# bubble_size_sensor.net
KiCad netlist of a schematic drawn in EAGLE
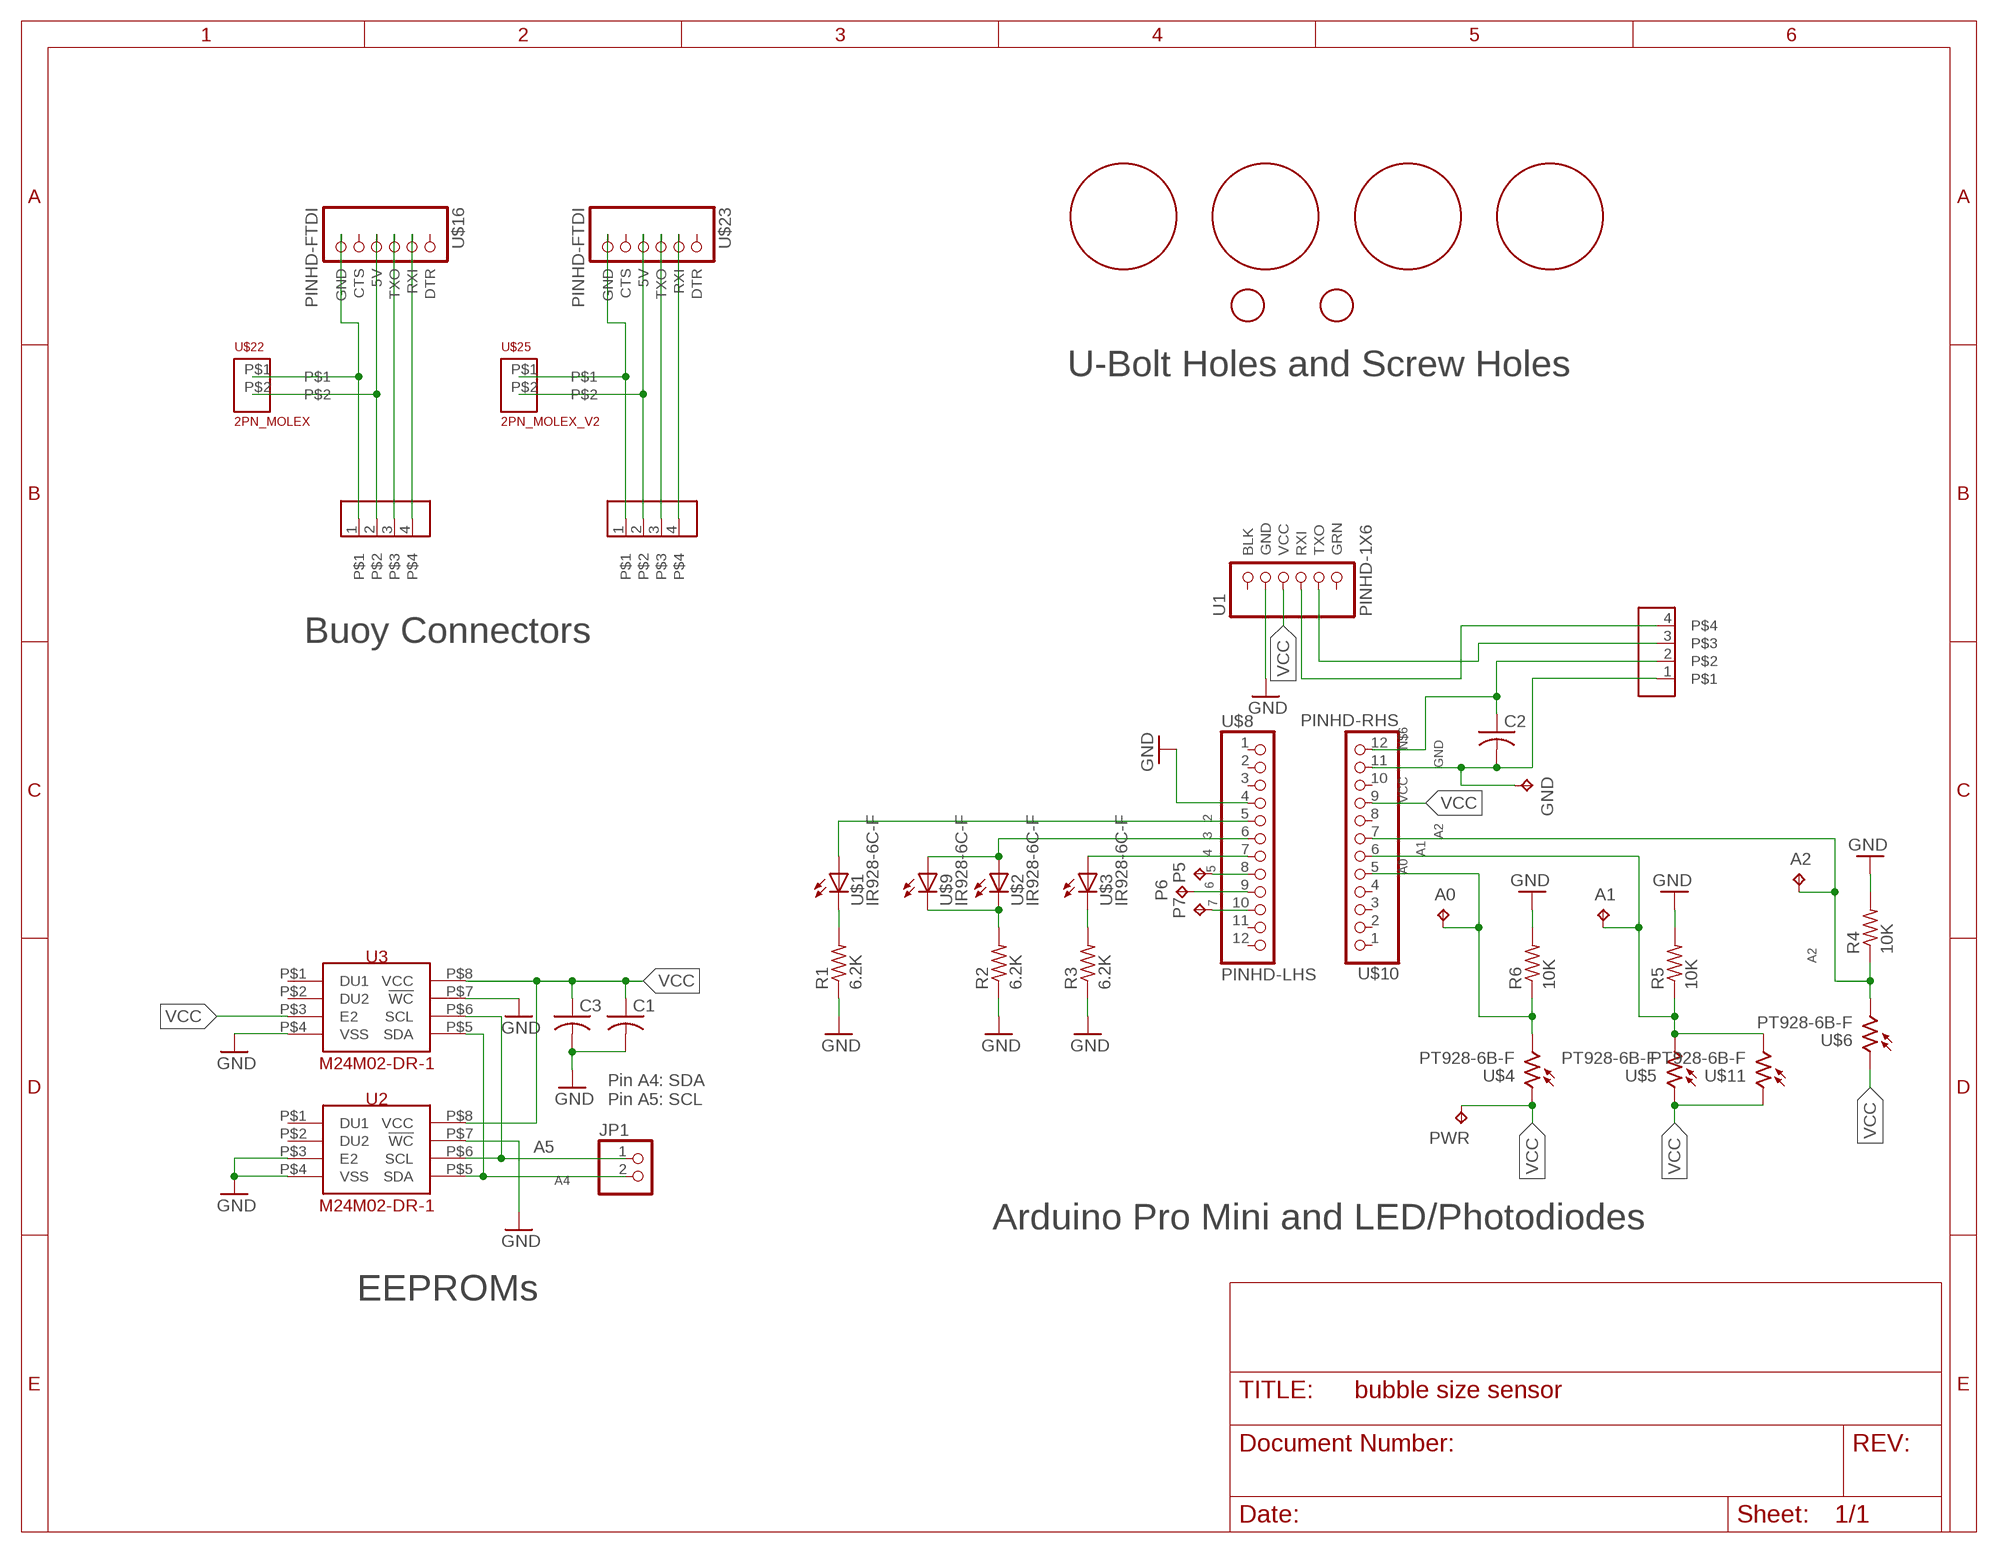
[diagram p0: schematic, sheet 1]

(export (version "E")
  (design (tool "Eeschema 10.0.6"))
  (components
    (comp (ref "A0")
      (value "TPPAD1-13")
      (footprint "eagle-import:P1-13")
      (libsource (lib "eagle-import") (part "TPPAD1-13"))
    )
    (comp (ref "A1")
      (value "TPPAD1-13")
      (footprint "eagle-import:P1-13")
      (libsource (lib "eagle-import") (part "TPPAD1-13"))
    )
    (comp (ref "A2")
      (value "TPPAD1-13")
      (footprint "eagle-import:P1-13")
      (libsource (lib "eagle-import") (part "TPPAD1-13"))
    )
    (comp (ref "C1")
      (value "C-USC0603")
      (footprint "eagle-import:C0603")
      (libsource (lib "eagle-import") (part "C-USC0603"))
    )
    (comp (ref "C2")
      (value "C-USC1210")
      (footprint "eagle-import:C1210")
      (libsource (lib "eagle-import") (part "C-USC1210"))
    )
    (comp (ref "C3")
      (value "C-USC0603")
      (footprint "eagle-import:C0603")
      (libsource (lib "eagle-import") (part "C-USC0603"))
    )
    (comp (ref "GND")
      (value "TPPAD1-13")
      (footprint "eagle-import:P1-13")
      (libsource (lib "eagle-import") (part "TPPAD1-13"))
    )
    (comp (ref "H$13")
      (value "M2_SCREW_HOLE")
      (footprint "eagle-import:M2_SCREW_HOLE")
      (libsource (lib "eagle-import") (part "M2_SCREW_HOLE"))
    )
    (comp (ref "H$15")
      (value "M2_SCREW_HOLE")
      (footprint "eagle-import:M2_SCREW_HOLE")
      (libsource (lib "eagle-import") (part "M2_SCREW_HOLE"))
    )
    (comp (ref "H$17")
      (value "UBOLT_HOLE")
      (footprint "eagle-import:UBOLT_HOLE")
      (libsource (lib "eagle-import") (part "UBOLT_HOLE"))
    )
    (comp (ref "H$18")
      (value "UBOLT_HOLE")
      (footprint "eagle-import:UBOLT_HOLE")
      (libsource (lib "eagle-import") (part "UBOLT_HOLE"))
    )
    (comp (ref "H$19")
      (value "UBOLT_HOLE")
      (footprint "eagle-import:UBOLT_HOLE")
      (libsource (lib "eagle-import") (part "UBOLT_HOLE"))
    )
    (comp (ref "H$20")
      (value "UBOLT_HOLE")
      (footprint "eagle-import:UBOLT_HOLE")
      (libsource (lib "eagle-import") (part "UBOLT_HOLE"))
    )
    (comp (ref "JP1")
      (value "PINHD-1X2")
      (footprint "eagle-import:1X02")
      (libsource (lib "eagle-import") (part "PINHD-1X2"))
    )
    (comp (ref "P5")
      (value "TPPAD1-13")
      (footprint "eagle-import:P1-13")
      (libsource (lib "eagle-import") (part "TPPAD1-13"))
    )
    (comp (ref "P6")
      (value "TPPAD1-13")
      (footprint "eagle-import:P1-13")
      (libsource (lib "eagle-import") (part "TPPAD1-13"))
    )
    (comp (ref "P7")
      (value "TPPAD1-13")
      (footprint "eagle-import:P1-13")
      (libsource (lib "eagle-import") (part "TPPAD1-13"))
    )
    (comp (ref "PWR")
      (value "TPPAD1-13")
      (footprint "eagle-import:P1-13")
      (libsource (lib "eagle-import") (part "TPPAD1-13"))
    )
    (comp (ref "R1")
      (value "6.2K")
      (footprint "eagle-import:R0603")
      (libsource (lib "eagle-import") (part "R-US_R0603"))
    )
    (comp (ref "R2")
      (value "6.2K")
      (footprint "eagle-import:R0603")
      (libsource (lib "eagle-import") (part "R-US_R0603"))
    )
    (comp (ref "R3")
      (value "6.2K")
      (footprint "eagle-import:R0603")
      (libsource (lib "eagle-import") (part "R-US_R0603"))
    )
    (comp (ref "R4")
      (value "10K")
      (footprint "eagle-import:R0603")
      (libsource (lib "eagle-import") (part "R-US_R0603"))
    )
    (comp (ref "R5")
      (value "10K")
      (footprint "eagle-import:R0603")
      (libsource (lib "eagle-import") (part "R-US_R0603"))
    )
    (comp (ref "R6")
      (value "10K")
      (footprint "eagle-import:R0603")
      (libsource (lib "eagle-import") (part "R-US_R0603"))
    )
    (comp (ref "U$1")
      (value "IR928-6C-F")
      (footprint "eagle-import:LED_LAYOUT")
      (libsource (lib "eagle-import") (part "IR928-6C-F"))
    )
    (comp (ref "U$2")
      (value "IR928-6C-F")
      (footprint "eagle-import:LED_LAYOUT")
      (libsource (lib "eagle-import") (part "IR928-6C-F"))
    )
    (comp (ref "U$3")
      (value "IR928-6C-F")
      (footprint "eagle-import:LED_LAYOUT")
      (libsource (lib "eagle-import") (part "IR928-6C-F"))
    )
    (comp (ref "U$4")
      (value "PT928-6B-F")
      (footprint "eagle-import:LED_LAYOUT")
      (libsource (lib "eagle-import") (part "PT928-6B-F"))
    )
    (comp (ref "U$5")
      (value "PT928-6B-F")
      (footprint "eagle-import:LED_LAYOUT")
      (libsource (lib "eagle-import") (part "PT928-6B-F"))
    )
    (comp (ref "U$6")
      (value "PT928-6B-F")
      (footprint "eagle-import:LED_LAYOUT")
      (libsource (lib "eagle-import") (part "PT928-6B-F"))
    )
    (comp (ref "U$8")
      (value "PINHD-LHS")
      (footprint "eagle-import:1X12")
      (libsource (lib "eagle-import") (part "PINHD-LHS"))
    )
    (comp (ref "U$9")
      (value "IR928-6C-F")
      (footprint "eagle-import:LED_LAYOUT")
      (libsource (lib "eagle-import") (part "IR928-6C-F"))
    )
    (comp (ref "U$10")
      (value "PINHD-RHS")
      (footprint "eagle-import:1X12")
      (libsource (lib "eagle-import") (part "PINHD-RHS"))
    )
    (comp (ref "U$11")
      (value "PT928-6B-F")
      (footprint "eagle-import:LED_LAYOUT")
      (libsource (lib "eagle-import") (part "PT928-6B-F"))
    )
    (comp (ref "U$14")
      (value "MICROFIT3.0_4POS_SMD")
      (footprint "eagle-import:MICRO_FIT3.0_4POS-SM")
      (libsource (lib "eagle-import") (part "MICROFIT3.0_4POS_SMD"))
    )
    (comp (ref "U$16")
      (value "PINHD-FTDI")
      (footprint "eagle-import:1X6")
      (libsource (lib "eagle-import") (part "PINHD-FTDI"))
    )
    (comp (ref "U$21")
      (value "MICROFIT3.0_4POS_SMD")
      (footprint "eagle-import:MICRO_FIT3.0_4POS-SM")
      (libsource (lib "eagle-import") (part "MICROFIT3.0_4POS_SMD"))
    )
    (comp (ref "U$22")
      (value "2PN_MOLEX")
      (footprint "eagle-import:2PN_MOLEX")
      (libsource (lib "eagle-import") (part "2PN_MOLEX"))
    )
    (comp (ref "U$23")
      (value "PINHD-FTDI")
      (footprint "eagle-import:1X6")
      (libsource (lib "eagle-import") (part "PINHD-FTDI"))
    )
    (comp (ref "U$24")
      (value "MICROFIT3.0_4POS_SMD")
      (footprint "eagle-import:MICRO_FIT3.0_4POS-SM")
      (libsource (lib "eagle-import") (part "MICROFIT3.0_4POS_SMD"))
    )
    (comp (ref "U$25")
      (value "2PN_MOLEX_V2")
      (footprint "eagle-import:2PN_MOLEX_V2")
      (libsource (lib "eagle-import") (part "2PN_MOLEX_V2"))
    )
    (comp (ref "U1")
      (value "PINHD-1X6")
      (footprint "eagle-import:1X6")
      (libsource (lib "eagle-import") (part "PINHD-1X6"))
    )
    (comp (ref "U2")
      (value "M24M02-DR-1")
      (footprint "eagle-import:SO8N")
      (fields
        (field (name "MANPARTNUMBER") "M24M02-DRMN6TP")
        (field (name "MANUFACTURER") "STMicroelectronics")
        (field (name "PARTNUMBER") "497-11600-1-ND")
      )
      (libsource (lib "eagle-import") (part "M24M02-DR-1"))
    )
    (comp (ref "U3")
      (value "M24M02-DR-1")
      (footprint "eagle-import:SO8N")
      (fields
        (field (name "MANPARTNUMBER") "M24M02-DRMN6TP")
        (field (name "MANUFACTURER") "STMicroelectronics")
        (field (name "PARTNUMBER") "497-11600-1-ND")
      )
      (libsource (lib "eagle-import") (part "M24M02-DR-1"))
    )
  )
  (nets
    (net (code "1") (name "/2") (class "Default")
      (node (ref "U$1") (pin "PWR") (pinfunction "PWR_PWR") (pintype "passive"))
      (node (ref "U$8") (pin "5") (pinfunction "2_5") (pintype "passive"))
    )
    (net (code "2") (name "/3") (class "Default")
      (node (ref "U$2") (pin "PWR") (pinfunction "PWR_PWR") (pintype "passive"))
      (node (ref "U$8") (pin "6") (pinfunction "3_6") (pintype "passive"))
      (node (ref "U$9") (pin "PWR") (pinfunction "PWR_PWR") (pintype "passive"))
    )
    (net (code "3") (name "/4") (class "Default")
      (node (ref "U$3") (pin "PWR") (pinfunction "PWR_PWR") (pintype "passive"))
      (node (ref "U$8") (pin "7") (pinfunction "4_7") (pintype "passive"))
    )
    (net (code "4") (name "/5") (class "Default")
      (node (ref "P5") (pin "TP") (pinfunction "TP_TP") (pintype "input"))
      (node (ref "U$8") (pin "8") (pinfunction "5_8") (pintype "passive"))
    )
    (net (code "5") (name "/6") (class "Default")
      (node (ref "P6") (pin "TP") (pinfunction "TP_TP") (pintype "input"))
      (node (ref "U$8") (pin "9") (pinfunction "6_9") (pintype "passive"))
    )
    (net (code "6") (name "/7") (class "Default")
      (node (ref "P7") (pin "TP") (pinfunction "TP_TP") (pintype "input"))
      (node (ref "U$8") (pin "10") (pinfunction "7_10") (pintype "passive"))
    )
    (net (code "7") (name "/A0") (class "Default")
      (node (ref "A0") (pin "TP") (pinfunction "TP_TP") (pintype "input"))
      (node (ref "R6") (pin "1") (pinfunction "1_1") (pintype "passive"))
      (node (ref "U$10") (pin "5") (pinfunction "A3_5") (pintype "passive"))
      (node (ref "U$4") (pin "RSTR") (pinfunction "RSTR_RSTR") (pintype "passive"))
    )
    (net (code "8") (name "/A1") (class "Default")
      (node (ref "A1") (pin "TP") (pinfunction "TP_TP") (pintype "input"))
      (node (ref "R5") (pin "1") (pinfunction "1_1") (pintype "passive"))
      (node (ref "U$10") (pin "6") (pinfunction "A2_6") (pintype "passive"))
      (node (ref "U$11") (pin "RSTR") (pinfunction "RSTR_RSTR") (pintype "passive"))
      (node (ref "U$5") (pin "RSTR") (pinfunction "RSTR_RSTR") (pintype "passive"))
    )
    (net (code "9") (name "/A2") (class "Default")
      (node (ref "A2") (pin "TP") (pinfunction "TP_TP") (pintype "input"))
      (node (ref "R4") (pin "1") (pinfunction "1_1") (pintype "passive"))
      (node (ref "U$10") (pin "7") (pinfunction "A1_7") (pintype "passive"))
      (node (ref "U$6") (pin "RSTR") (pinfunction "RSTR_RSTR") (pintype "passive"))
    )
    (net (code "10") (name "/A4") (class "Default")
      (node (ref "JP1") (pin "2") (pinfunction "2_2") (pintype "passive"))
      (node (ref "U2") (pin "P$5") (pinfunction "SDA_P$5") (pintype "bidirectional"))
      (node (ref "U3") (pin "P$5") (pinfunction "SDA_P$5") (pintype "bidirectional"))
    )
    (net (code "11") (name "/A5") (class "Default")
      (node (ref "JP1") (pin "1") (pinfunction "1_1") (pintype "passive"))
      (node (ref "U2") (pin "P$6") (pinfunction "SCL_P$6") (pintype "input"))
      (node (ref "U3") (pin "P$6") (pinfunction "SCL_P$6") (pintype "input"))
    )
    (net (code "12") (name "/N$6") (class "Default")
      (node (ref "C2") (pin "1") (pinfunction "1_1") (pintype "passive"))
      (node (ref "U$10") (pin "12") (pinfunction "10_12") (pintype "passive"))
      (node (ref "U$14") (pin "2") (pinfunction "P$2_2") (pintype "bidirectional"))
    )
    (net (code "13") (name "GND") (class "Default")
      (node (ref "C1") (pin "2") (pinfunction "2_2") (pintype "passive"))
      (node (ref "C2") (pin "2") (pinfunction "2_2") (pintype "passive"))
      (node (ref "C3") (pin "2") (pinfunction "2_2") (pintype "passive"))
      (node (ref "GND") (pin "TP") (pinfunction "TP_TP") (pintype "input"))
      (node (ref "R1") (pin "1") (pinfunction "1_1") (pintype "passive"))
      (node (ref "R2") (pin "1") (pinfunction "1_1") (pintype "passive"))
      (node (ref "R3") (pin "1") (pinfunction "1_1") (pintype "passive"))
      (node (ref "R4") (pin "2") (pinfunction "2_2") (pintype "passive"))
      (node (ref "R5") (pin "2") (pinfunction "2_2") (pintype "passive"))
      (node (ref "R6") (pin "2") (pinfunction "2_2") (pintype "passive"))
      (node (ref "U$10") (pin "11") (pinfunction "11_11") (pintype "passive"))
      (node (ref "U$14") (pin "1") (pinfunction "P$1_1") (pintype "bidirectional"))
      (node (ref "U$8") (pin "4") (pinfunction "GND_4") (pintype "passive"))
      (node (ref "U1") (pin "2") (pinfunction "GND_2") (pintype "bidirectional"))
      (node (ref "U2") (pin "P$3") (pinfunction "E2_P$3") (pintype "input"))
      (node (ref "U2") (pin "P$4") (pinfunction "VSS_P$4") (pintype "power_in"))
      (node (ref "U2") (pin "P$7") (pinfunction "~{WC}_P$7") (pintype "input"))
      (node (ref "U3") (pin "P$4") (pinfunction "VSS_P$4") (pintype "power_in"))
      (node (ref "U3") (pin "P$7") (pinfunction "~{WC}_P$7") (pintype "input"))
    )
    (net (code "14") (name "Net-(R1-Pad2)") (class "Default")
      (node (ref "R1") (pin "2") (pinfunction "2_2") (pintype "passive"))
      (node (ref "U$1") (pin "RSTR") (pinfunction "RSTR_RSTR") (pintype "passive"))
    )
    (net (code "15") (name "Net-(R2-Pad2)") (class "Default")
      (node (ref "R2") (pin "2") (pinfunction "2_2") (pintype "passive"))
      (node (ref "U$2") (pin "RSTR") (pinfunction "RSTR_RSTR") (pintype "passive"))
      (node (ref "U$9") (pin "RSTR") (pinfunction "RSTR_RSTR") (pintype "passive"))
    )
    (net (code "16") (name "Net-(R3-Pad2)") (class "Default")
      (node (ref "R3") (pin "2") (pinfunction "2_2") (pintype "passive"))
      (node (ref "U$3") (pin "RSTR") (pinfunction "RSTR_RSTR") (pintype "passive"))
    )
    (net (code "17") (name "Net-(U$14-P$3)") (class "Default")
      (node (ref "U$14") (pin "3") (pinfunction "P$3_3") (pintype "bidirectional"))
      (node (ref "U1") (pin "5") (pinfunction "TXO_5") (pintype "bidirectional"))
    )
    (net (code "18") (name "Net-(U$14-P$4)") (class "Default")
      (node (ref "U$14") (pin "4") (pinfunction "P$4_4") (pintype "bidirectional"))
      (node (ref "U1") (pin "4") (pinfunction "RXI_4") (pintype "bidirectional"))
    )
    (net (code "19") (name "Net-(U$16-5V)") (class "Default")
      (node (ref "U$16") (pin "4") (pinfunction "5V_4") (pintype "bidirectional"))
      (node (ref "U$21") (pin "2") (pinfunction "P$2_2") (pintype "bidirectional"))
      (node (ref "U$22") (pin "P$2") (pinfunction "P$2_P$2") (pintype "bidirectional"))
    )
    (net (code "20") (name "Net-(U$16-GND)") (class "Default")
      (node (ref "U$16") (pin "6") (pinfunction "GND_6") (pintype "bidirectional"))
      (node (ref "U$21") (pin "1") (pinfunction "P$1_1") (pintype "bidirectional"))
      (node (ref "U$22") (pin "P$1") (pinfunction "P$1_P$1") (pintype "bidirectional"))
    )
    (net (code "21") (name "Net-(U$16-RXI)") (class "Default")
      (node (ref "U$16") (pin "2") (pinfunction "RXI_2") (pintype "bidirectional"))
      (node (ref "U$21") (pin "4") (pinfunction "P$4_4") (pintype "bidirectional"))
    )
    (net (code "22") (name "Net-(U$16-TXO)") (class "Default")
      (node (ref "U$16") (pin "3") (pinfunction "TXO_3") (pintype "bidirectional"))
      (node (ref "U$21") (pin "3") (pinfunction "P$3_3") (pintype "bidirectional"))
    )
    (net (code "23") (name "Net-(U$23-5V)") (class "Default")
      (node (ref "U$23") (pin "4") (pinfunction "5V_4") (pintype "bidirectional"))
      (node (ref "U$24") (pin "2") (pinfunction "P$2_2") (pintype "bidirectional"))
      (node (ref "U$25") (pin "P$2") (pinfunction "P$2_P$2") (pintype "bidirectional"))
    )
    (net (code "24") (name "Net-(U$23-GND)") (class "Default")
      (node (ref "U$23") (pin "6") (pinfunction "GND_6") (pintype "bidirectional"))
      (node (ref "U$24") (pin "1") (pinfunction "P$1_1") (pintype "bidirectional"))
      (node (ref "U$25") (pin "P$1") (pinfunction "P$1_P$1") (pintype "bidirectional"))
    )
    (net (code "25") (name "Net-(U$23-RXI)") (class "Default")
      (node (ref "U$23") (pin "2") (pinfunction "RXI_2") (pintype "bidirectional"))
      (node (ref "U$24") (pin "4") (pinfunction "P$4_4") (pintype "bidirectional"))
    )
    (net (code "26") (name "Net-(U$23-TXO)") (class "Default")
      (node (ref "U$23") (pin "3") (pinfunction "TXO_3") (pintype "bidirectional"))
      (node (ref "U$24") (pin "3") (pinfunction "P$3_3") (pintype "bidirectional"))
    )
    (net (code "27") (name "VCC") (class "Default")
      (node (ref "C1") (pin "1") (pinfunction "1_1") (pintype "passive"))
      (node (ref "C3") (pin "1") (pinfunction "1_1") (pintype "passive"))
      (node (ref "PWR") (pin "TP") (pinfunction "TP_TP") (pintype "input"))
      (node (ref "U$10") (pin "9") (pinfunction "13_9") (pintype "passive"))
      (node (ref "U$11") (pin "PWR") (pinfunction "PWR_PWR") (pintype "passive"))
      (node (ref "U$4") (pin "PWR") (pinfunction "PWR_PWR") (pintype "passive"))
      (node (ref "U$5") (pin "PWR") (pinfunction "PWR_PWR") (pintype "passive"))
      (node (ref "U$6") (pin "PWR") (pinfunction "PWR_PWR") (pintype "passive"))
      (node (ref "U1") (pin "3") (pinfunction "VCC_3") (pintype "bidirectional"))
      (node (ref "U2") (pin "P$8") (pinfunction "VCC_P$8") (pintype "power_in"))
      (node (ref "U3") (pin "P$3") (pinfunction "E2_P$3") (pintype "input"))
      (node (ref "U3") (pin "P$8") (pinfunction "VCC_P$8") (pintype "power_in"))
    )
    (net (code "28") (name "unconnected-(U$8-8-Pad11)") (class "Default")
      (node (ref "U$8") (pin "11") (pinfunction "8_11") (pintype "passive"))
    )
    (net (code "29") (name "unconnected-(U$8-9-Pad12)") (class "Default")
      (node (ref "U$8") (pin "12") (pinfunction "9_12") (pintype "passive"))
    )
    (net (code "30") (name "unconnected-(U$8-RST-Pad3)") (class "Default")
      (node (ref "U$8") (pin "3") (pinfunction "RST_3") (pintype "passive"))
    )
    (net (code "31") (name "unconnected-(U$8-RXI-Pad2)") (class "Default")
      (node (ref "U$8") (pin "2") (pinfunction "RXI_2") (pintype "passive"))
    )
    (net (code "32") (name "unconnected-(U$8-TXO-Pad1)") (class "Default")
      (node (ref "U$8") (pin "1") (pinfunction "TXO_1") (pintype "passive"))
    )
    (net (code "33") (name "unconnected-(U$10-12-Pad10)") (class "Default")
      (node (ref "U$10") (pin "10") (pinfunction "12_10") (pintype "passive"))
    )
    (net (code "34") (name "unconnected-(U$10-A0-Pad8)") (class "Default")
      (node (ref "U$10") (pin "8") (pinfunction "A0_8") (pintype "passive"))
    )
    (net (code "35") (name "unconnected-(U$10-GND2-Pad2)") (class "Default")
      (node (ref "U$10") (pin "2") (pinfunction "GND2_2") (pintype "passive"))
    )
    (net (code "36") (name "unconnected-(U$10-RAW-Pad1)") (class "Default")
      (node (ref "U$10") (pin "1") (pinfunction "RAW_1") (pintype "passive"))
    )
    (net (code "37") (name "unconnected-(U$10-RST-Pad3)") (class "Default")
      (node (ref "U$10") (pin "3") (pinfunction "RST_3") (pintype "passive"))
    )
    (net (code "38") (name "unconnected-(U$10-VCC-Pad4)") (class "Default")
      (node (ref "U$10") (pin "4") (pinfunction "VCC_4") (pintype "passive"))
    )
    (net (code "39") (name "unconnected-(U$16-CTS-Pad5)") (class "Default")
      (node (ref "U$16") (pin "5") (pinfunction "CTS_5") (pintype "bidirectional"))
    )
    (net (code "40") (name "unconnected-(U$16-DTR-Pad1)") (class "Default")
      (node (ref "U$16") (pin "1") (pinfunction "DTR_1") (pintype "bidirectional"))
    )
    (net (code "41") (name "unconnected-(U$23-CTS-Pad5)") (class "Default")
      (node (ref "U$23") (pin "5") (pinfunction "CTS_5") (pintype "bidirectional"))
    )
    (net (code "42") (name "unconnected-(U$23-DTR-Pad1)") (class "Default")
      (node (ref "U$23") (pin "1") (pinfunction "DTR_1") (pintype "bidirectional"))
    )
    (net (code "43") (name "unconnected-(U1-BLK-Pad1)") (class "Default")
      (node (ref "U1") (pin "1") (pinfunction "BLK_1") (pintype "bidirectional"))
    )
    (net (code "44") (name "unconnected-(U1-GRN-Pad6)") (class "Default")
      (node (ref "U1") (pin "6") (pinfunction "GRN_6") (pintype "bidirectional"))
    )
    (net (code "45") (name "unconnected-(U2-DU1-PadP$1)") (class "Default")
      (node (ref "U2") (pin "P$1") (pinfunction "DU1_P$1") (pintype "no_connect"))
    )
    (net (code "46") (name "unconnected-(U2-DU2-PadP$2)") (class "Default")
      (node (ref "U2") (pin "P$2") (pinfunction "DU2_P$2") (pintype "no_connect"))
    )
    (net (code "47") (name "unconnected-(U3-DU1-PadP$1)") (class "Default")
      (node (ref "U3") (pin "P$1") (pinfunction "DU1_P$1") (pintype "no_connect"))
    )
    (net (code "48") (name "unconnected-(U3-DU2-PadP$2)") (class "Default")
      (node (ref "U3") (pin "P$2") (pinfunction "DU2_P$2") (pintype "no_connect"))
    )
  )
)
